# mdv_commutator.net
KiCad netlist of a schematic drawn in Altium Designer
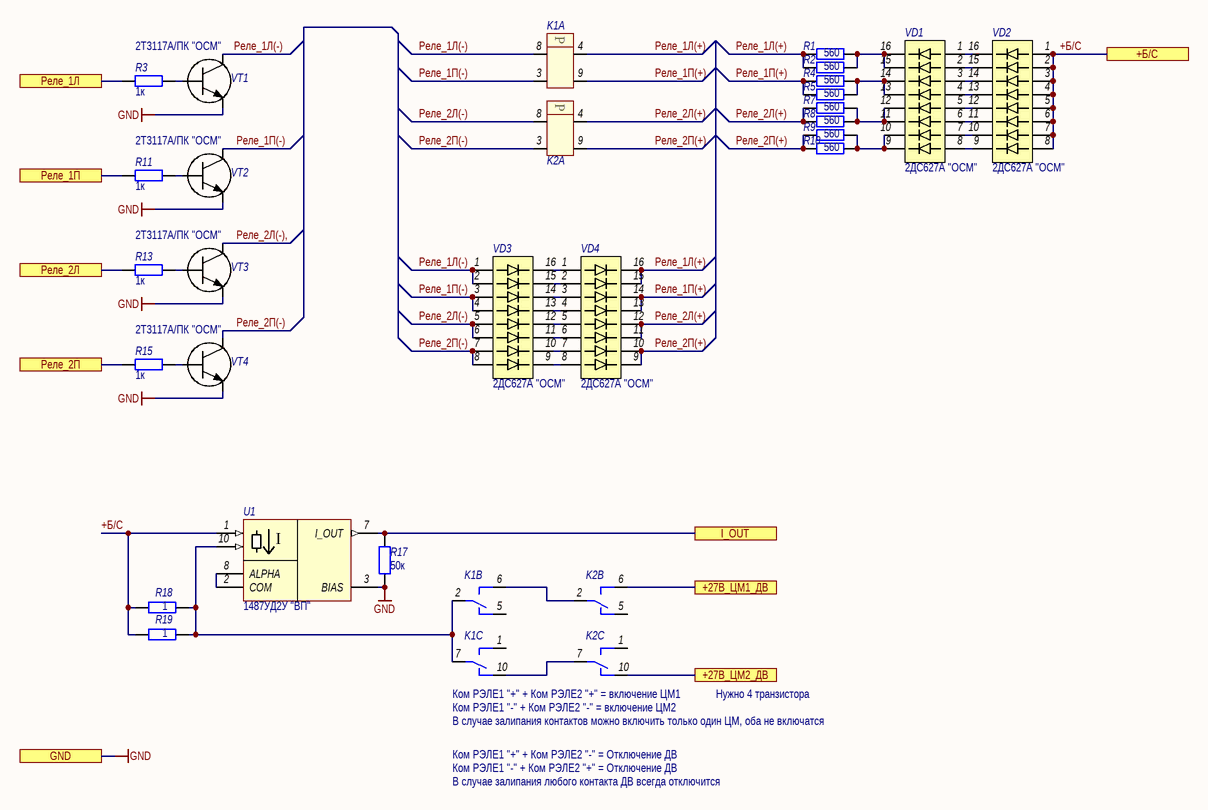
[diagram p0: mdv_commutator.SchDoc]

(export (version "E")
  (design (tool "Eeschema 10.0.6"))
  (components
    (comp (ref "K1")
      (value "RPS45-1-T-OS")
      (footprint "RPS-45-1")
      (description "Реле поляризованное")
      (libsource (lib "") (part "RPS45_1"))
    )
    (comp (ref "K2")
      (value "RPS45-1-T-OS")
      (footprint "RPS-45-1")
      (description "Реле поляризованное")
      (libsource (lib "Commutator") (part "RPS45"))
    )
    (comp (ref "R1")
      (value "560")
      (footprint "SMD_0805")
      (description "Resistor")
      (libsource (lib "Passive") (part "Resistor"))
    )
    (comp (ref "R2")
      (value "560")
      (footprint "SMD_0805")
      (description "Resistor")
      (libsource (lib "Passive") (part "Resistor"))
    )
    (comp (ref "R3")
      (value "1к")
      (footprint "SMD_0805")
      (description "Resistor")
      (libsource (lib "Passive") (part "Resistor"))
    )
    (comp (ref "R4")
      (value "560")
      (footprint "SMD_0805")
      (description "Resistor")
      (libsource (lib "Passive") (part "Resistor"))
    )
    (comp (ref "R5")
      (value "560")
      (footprint "SMD_0805")
      (description "Resistor")
      (libsource (lib "Passive") (part "Resistor"))
    )
    (comp (ref "R7")
      (value "560")
      (footprint "SMD_0805")
      (description "Resistor")
      (libsource (lib "Passive") (part "Resistor"))
    )
    (comp (ref "R8")
      (value "560")
      (footprint "SMD_0805")
      (description "Resistor")
      (libsource (lib "Passive") (part "Resistor"))
    )
    (comp (ref "R9")
      (value "560")
      (footprint "SMD_0805")
      (description "Resistor")
      (libsource (lib "Passive") (part "Resistor"))
    )
    (comp (ref "R10")
      (value "560")
      (footprint "SMD_0805")
      (description "Resistor")
      (libsource (lib "Passive") (part "Resistor"))
    )
    (comp (ref "R11")
      (value "1к")
      (footprint "SMD_0805")
      (description "Resistor")
      (libsource (lib "Passive") (part "Resistor"))
    )
    (comp (ref "R13")
      (value "1к")
      (footprint "SMD_0805")
      (description "Resistor")
      (libsource (lib "Passive") (part "Resistor"))
    )
    (comp (ref "R15")
      (value "1к")
      (footprint "SMD_0805")
      (description "Resistor")
      (libsource (lib "Passive") (part "Resistor"))
    )
    (comp (ref "R17")
      (value "50к")
      (footprint "SMD_0805")
      (description "Resistor")
      (libsource (lib "") (part "Resistor_2"))
    )
    (comp (ref "R18")
      (value "1")
      (footprint "SMD_0805")
      (description "Resistor")
      (libsource (lib "") (part "Resistor_1"))
    )
    (comp (ref "R19")
      (value "1")
      (footprint "SMD_0805")
      (description "Resistor")
      (libsource (lib "") (part "Resistor_1"))
    )
    (comp (ref "U1")
      (value "1487УД2У \"ВП\"")
      (footprint "FlatPack-10_MSOP-8")
      (libsource (lib "Power_Monitor") (part "AD8212S"))
    )
    (comp (ref "VD1")
      (value "2DS627A OSM")
      (footprint "401.16-3")
      (description "Диодная матрица")
      (fields (field (name "НАИМЕНОВАНИЕ") "2ДС627А \"ОСМ\""))
      (libsource (lib "Diod") (part "2DS627A"))
    )
    (comp (ref "VD2")
      (value "2DS627A OSM")
      (footprint "401.16-3")
      (description "Диодная матрица")
      (fields (field (name "НАИМЕНОВАНИЕ") "2ДС627А \"ОСМ\""))
      (libsource (lib "Diod") (part "2DS627A"))
    )
    (comp (ref "VD3")
      (value "2DS627A OSM")
      (footprint "401.16-3")
      (description "Диодная матрица")
      (fields (field (name "НАИМЕНОВАНИЕ") "2ДС627А \"ОСМ\""))
      (libsource (lib "Diod") (part "2DS627A"))
    )
    (comp (ref "VD4")
      (value "2DS627A OSM")
      (footprint "401.16-3")
      (description "Диодная матрица")
      (fields (field (name "НАИМЕНОВАНИЕ") "2ДС627А \"ОСМ\""))
      (libsource (lib "Diod") (part "2DS627A"))
    )
    (comp (ref "VT1")
      (value "2T3117A")
      (footprint "TO-18")
      (description "Кремниевый биполярный\r\nэпитаксиально-планарный\r\nn-p-n транзистор")
      (fields (field (name "НАИМЕНОВАНИЕ") "2Т3117А/ПК \"ОСМ\""))
      (libsource (lib "Transistor") (part "2T3117A"))
    )
    (comp (ref "VT2")
      (value "2T3117A")
      (footprint "TO-18")
      (description "Кремниевый биполярный\r\nэпитаксиально-планарный\r\nn-p-n транзистор")
      (fields (field (name "НАИМЕНОВАНИЕ") "2Т3117А/ПК \"ОСМ\""))
      (libsource (lib "Transistor") (part "2T3117A"))
    )
    (comp (ref "VT3")
      (value "2T3117A")
      (footprint "TO-18")
      (description "Кремниевый биполярный\r\nэпитаксиально-планарный\r\nn-p-n транзистор")
      (fields (field (name "НАИМЕНОВАНИЕ") "2Т3117А/ПК \"ОСМ\""))
      (libsource (lib "Transistor") (part "2T3117A"))
    )
    (comp (ref "VT4")
      (value "2T3117A")
      (footprint "TO-18")
      (description "Кремниевый биполярный\r\nэпитаксиально-планарный\r\nn-p-n транзистор")
      (fields (field (name "НАИМЕНОВАНИЕ") "2Т3117А/ПК \"ОСМ\""))
      (libsource (lib "Transistor") (part "2T3117A"))
    )
  )
  (nets
    (net (code "1") (name "/+27В_ЦМ1_ДВ") (class "Default")
      (node (ref "K2") (pin "6") (pinfunction "6_6") (pintype "passive"))
    )
    (net (code "2") (name "/+27В_ЦМ2_ДВ") (class "Default")
      (node (ref "K2") (pin "10") (pinfunction "10_10") (pintype "passive"))
    )
    (net (code "3") (name "/+Б{slash}С") (class "Default")
      (node (ref "R18") (pin "2") (pinfunction "2_2") (pintype "passive"))
      (node (ref "R19") (pin "2") (pinfunction "2_2") (pintype "passive"))
      (node (ref "U1") (pin "1") (pinfunction "V+_1") (pintype "input"))
      (node (ref "VD2") (pin "1") (pinfunction "1A_1") (pintype "passive"))
      (node (ref "VD2") (pin "2") (pinfunction "1B_2") (pintype "passive"))
      (node (ref "VD2") (pin "3") (pinfunction "1C_3") (pintype "passive"))
      (node (ref "VD2") (pin "4") (pinfunction "1D_4") (pintype "passive"))
      (node (ref "VD2") (pin "5") (pinfunction "1E_5") (pintype "passive"))
      (node (ref "VD2") (pin "6") (pinfunction "1F_6") (pintype "passive"))
      (node (ref "VD2") (pin "7") (pinfunction "1G_7") (pintype "passive"))
      (node (ref "VD2") (pin "8") (pinfunction "1H_8") (pintype "passive"))
    )
    (net (code "4") (name "/I_OUT") (class "Default")
      (node (ref "R17") (pin "2") (pinfunction "2_2") (pintype "passive"))
      (node (ref "U1") (pin "7") (pinfunction "I_OUT_7") (pintype "output"))
    )
    (net (code "5") (name "/Реле_1Л") (class "Default")
      (node (ref "R3") (pin "1") (pinfunction "1_1") (pintype "passive"))
    )
    (net (code "6") (name "/Реле_1Л(+)") (class "Default")
      (node (ref "K1") (pin "4") (pinfunction "4_4") (pintype "passive"))
      (node (ref "R1") (pin "1") (pinfunction "1_1") (pintype "passive"))
      (node (ref "R2") (pin "1") (pinfunction "1_1") (pintype "passive"))
      (node (ref "VD4") (pin "15") (pinfunction "2B_15") (pintype "passive"))
      (node (ref "VD4") (pin "16") (pinfunction "2A_16") (pintype "passive"))
    )
    (net (code "7") (name "/Реле_1Л(-)") (class "Default")
      (node (ref "K1") (pin "8") (pinfunction "8_8") (pintype "passive"))
      (node (ref "VD3") (pin "1") (pinfunction "1A_1") (pintype "passive"))
      (node (ref "VD3") (pin "2") (pinfunction "1B_2") (pintype "passive"))
      (node (ref "VT1") (pin "3") (pinfunction "COLLECTOR_3") (pintype "passive"))
    )
    (net (code "8") (name "/Реле_1П") (class "Default")
      (node (ref "R11") (pin "1") (pinfunction "1_1") (pintype "passive"))
    )
    (net (code "9") (name "/Реле_1П(+)") (class "Default")
      (node (ref "K1") (pin "9") (pinfunction "9_9") (pintype "passive"))
      (node (ref "R4") (pin "1") (pinfunction "1_1") (pintype "passive"))
      (node (ref "R5") (pin "1") (pinfunction "1_1") (pintype "passive"))
      (node (ref "VD4") (pin "13") (pinfunction "2D_13") (pintype "passive"))
      (node (ref "VD4") (pin "14") (pinfunction "2C_14") (pintype "passive"))
    )
    (net (code "10") (name "/Реле_1П(-)") (class "Default")
      (node (ref "K1") (pin "3") (pinfunction "3_3") (pintype "passive"))
      (node (ref "VD3") (pin "3") (pinfunction "1C_3") (pintype "passive"))
      (node (ref "VD3") (pin "4") (pinfunction "1D_4") (pintype "passive"))
      (node (ref "VT2") (pin "3") (pinfunction "COLLECTOR_3") (pintype "passive"))
    )
    (net (code "11") (name "/Реле_2Л") (class "Default")
      (node (ref "R13") (pin "1") (pinfunction "1_1") (pintype "passive"))
    )
    (net (code "12") (name "/Реле_2Л(+)") (class "Default")
      (node (ref "K2") (pin "4") (pinfunction "4_4") (pintype "passive"))
      (node (ref "R7") (pin "1") (pinfunction "1_1") (pintype "passive"))
      (node (ref "R8") (pin "1") (pinfunction "1_1") (pintype "passive"))
      (node (ref "VD4") (pin "11") (pinfunction "2F_11") (pintype "passive"))
      (node (ref "VD4") (pin "12") (pinfunction "2E_12") (pintype "passive"))
    )
    (net (code "13") (name "/Реле_2Л(-)") (class "Default")
      (node (ref "K2") (pin "8") (pinfunction "8_8") (pintype "passive"))
      (node (ref "VD3") (pin "5") (pinfunction "1E_5") (pintype "passive"))
      (node (ref "VD3") (pin "6") (pinfunction "1F_6") (pintype "passive"))
    )
    (net (code "14") (name "/Реле_2Л(-),") (class "Default")
      (node (ref "VT3") (pin "3") (pinfunction "COLLECTOR_3") (pintype "passive"))
    )
    (net (code "15") (name "/Реле_2П") (class "Default")
      (node (ref "R15") (pin "1") (pinfunction "1_1") (pintype "passive"))
    )
    (net (code "16") (name "/Реле_2П(+)") (class "Default")
      (node (ref "K2") (pin "9") (pinfunction "9_9") (pintype "passive"))
      (node (ref "R10") (pin "1") (pinfunction "1_1") (pintype "passive"))
      (node (ref "R9") (pin "1") (pinfunction "1_1") (pintype "passive"))
      (node (ref "VD4") (pin "10") (pinfunction "2G_10") (pintype "passive"))
      (node (ref "VD4") (pin "9") (pinfunction "2G_9") (pintype "passive"))
    )
    (net (code "17") (name "/Реле_2П(-)") (class "Default")
      (node (ref "K2") (pin "3") (pinfunction "3_3") (pintype "passive"))
      (node (ref "VD3") (pin "7") (pinfunction "1G_7") (pintype "passive"))
      (node (ref "VD3") (pin "8") (pinfunction "1H_8") (pintype "passive"))
      (node (ref "VT4") (pin "3") (pinfunction "COLLECTOR_3") (pintype "passive"))
    )
    (net (code "18") (name "GND") (class "Default")
      (node (ref "R17") (pin "1") (pinfunction "1_1") (pintype "passive"))
      (node (ref "U1") (pin "3") (pinfunction "BIAS_3") (pintype "open_collector"))
      (node (ref "VT1") (pin "1") (pinfunction "EMITTER_1") (pintype "passive"))
      (node (ref "VT2") (pin "1") (pinfunction "EMITTER_1") (pintype "passive"))
      (node (ref "VT3") (pin "1") (pinfunction "EMITTER_1") (pintype "passive"))
      (node (ref "VT4") (pin "1") (pinfunction "EMITTER_1") (pintype "passive"))
    )
    (net (code "19") (name "Net-(K1-Pad6)") (class "Default")
      (node (ref "K1") (pin "6") (pinfunction "6_6") (pintype "passive"))
      (node (ref "K2") (pin "2") (pinfunction "2_2") (pintype "passive"))
    )
    (net (code "20") (name "Net-(K1-Pad10)") (class "Default")
      (node (ref "K1") (pin "10") (pinfunction "10_10") (pintype "passive"))
      (node (ref "K2") (pin "7") (pinfunction "7_7") (pintype "passive"))
    )
    (net (code "21") (name "Net-(R10-Pad2)") (class "Default")
      (node (ref "R10") (pin "2") (pinfunction "2_2") (pintype "passive"))
      (node (ref "R9") (pin "2") (pinfunction "2_2") (pintype "passive"))
      (node (ref "VD1") (pin "10") (pinfunction "2G_10") (pintype "passive"))
      (node (ref "VD1") (pin "9") (pinfunction "2G_9") (pintype "passive"))
    )
    (net (code "22") (name "Net-(U1-ALPHA)") (class "Default")
      (node (ref "U1") (pin "2") (pinfunction "COM_2") (pintype "open_collector"))
      (node (ref "U1") (pin "8") (pinfunction "ALPHA_8") (pintype "open_collector"))
    )
    (net (code "23") (name "Net-(U1-V_SENSE)") (class "Default")
      (node (ref "K1") (pin "2") (pinfunction "2_2") (pintype "passive"))
      (node (ref "K1") (pin "7") (pinfunction "7_7") (pintype "passive"))
      (node (ref "R18") (pin "1") (pinfunction "1_1") (pintype "passive"))
      (node (ref "R19") (pin "1") (pinfunction "1_1") (pintype "passive"))
      (node (ref "U1") (pin "10") (pinfunction "V_SENSE_10") (pintype "input"))
    )
    (net (code "24") (name "Net-(VD1-1A)") (class "Default")
      (node (ref "VD1") (pin "1") (pinfunction "1A_1") (pintype "passive"))
      (node (ref "VD2") (pin "16") (pinfunction "2A_16") (pintype "passive"))
    )
    (net (code "25") (name "Net-(VD1-1B)") (class "Default")
      (node (ref "VD1") (pin "2") (pinfunction "1B_2") (pintype "passive"))
      (node (ref "VD2") (pin "15") (pinfunction "2B_15") (pintype "passive"))
    )
    (net (code "26") (name "Net-(VD1-1C)") (class "Default")
      (node (ref "VD1") (pin "3") (pinfunction "1C_3") (pintype "passive"))
      (node (ref "VD2") (pin "14") (pinfunction "2C_14") (pintype "passive"))
    )
    (net (code "27") (name "Net-(VD1-1D)") (class "Default")
      (node (ref "VD1") (pin "4") (pinfunction "1D_4") (pintype "passive"))
      (node (ref "VD2") (pin "13") (pinfunction "2D_13") (pintype "passive"))
    )
    (net (code "28") (name "Net-(VD1-1E)") (class "Default")
      (node (ref "VD1") (pin "5") (pinfunction "1E_5") (pintype "passive"))
      (node (ref "VD2") (pin "12") (pinfunction "2E_12") (pintype "passive"))
    )
    (net (code "29") (name "Net-(VD1-1F)") (class "Default")
      (node (ref "VD1") (pin "6") (pinfunction "1F_6") (pintype "passive"))
      (node (ref "VD2") (pin "11") (pinfunction "2F_11") (pintype "passive"))
    )
    (net (code "30") (name "Net-(VD1-1G)") (class "Default")
      (node (ref "VD1") (pin "7") (pinfunction "1G_7") (pintype "passive"))
      (node (ref "VD2") (pin "10") (pinfunction "2G_10") (pintype "passive"))
    )
    (net (code "31") (name "Net-(VD1-1H)") (class "Default")
      (node (ref "VD1") (pin "8") (pinfunction "1H_8") (pintype "passive"))
      (node (ref "VD2") (pin "9") (pinfunction "2G_9") (pintype "passive"))
    )
    (net (code "32") (name "Net-(VD1-2A)") (class "Default")
      (node (ref "R1") (pin "2") (pinfunction "2_2") (pintype "passive"))
      (node (ref "R2") (pin "2") (pinfunction "2_2") (pintype "passive"))
      (node (ref "VD1") (pin "15") (pinfunction "2B_15") (pintype "passive"))
      (node (ref "VD1") (pin "16") (pinfunction "2A_16") (pintype "passive"))
    )
    (net (code "33") (name "Net-(VD1-2C)") (class "Default")
      (node (ref "R4") (pin "2") (pinfunction "2_2") (pintype "passive"))
      (node (ref "R5") (pin "2") (pinfunction "2_2") (pintype "passive"))
      (node (ref "VD1") (pin "13") (pinfunction "2D_13") (pintype "passive"))
      (node (ref "VD1") (pin "14") (pinfunction "2C_14") (pintype "passive"))
    )
    (net (code "34") (name "Net-(VD1-2E)") (class "Default")
      (node (ref "R7") (pin "2") (pinfunction "2_2") (pintype "passive"))
      (node (ref "R8") (pin "2") (pinfunction "2_2") (pintype "passive"))
      (node (ref "VD1") (pin "11") (pinfunction "2F_11") (pintype "passive"))
      (node (ref "VD1") (pin "12") (pinfunction "2E_12") (pintype "passive"))
    )
    (net (code "35") (name "Net-(VD3-2A)") (class "Default")
      (node (ref "VD3") (pin "16") (pinfunction "2A_16") (pintype "passive"))
      (node (ref "VD4") (pin "1") (pinfunction "1A_1") (pintype "passive"))
    )
    (net (code "36") (name "Net-(VD3-2B)") (class "Default")
      (node (ref "VD3") (pin "15") (pinfunction "2B_15") (pintype "passive"))
      (node (ref "VD4") (pin "2") (pinfunction "1B_2") (pintype "passive"))
    )
    (net (code "37") (name "Net-(VD3-2C)") (class "Default")
      (node (ref "VD3") (pin "14") (pinfunction "2C_14") (pintype "passive"))
      (node (ref "VD4") (pin "3") (pinfunction "1C_3") (pintype "passive"))
    )
    (net (code "38") (name "Net-(VD3-2D)") (class "Default")
      (node (ref "VD3") (pin "13") (pinfunction "2D_13") (pintype "passive"))
      (node (ref "VD4") (pin "4") (pinfunction "1D_4") (pintype "passive"))
    )
    (net (code "39") (name "Net-(VD3-2E)") (class "Default")
      (node (ref "VD3") (pin "12") (pinfunction "2E_12") (pintype "passive"))
      (node (ref "VD4") (pin "5") (pinfunction "1E_5") (pintype "passive"))
    )
    (net (code "40") (name "Net-(VD3-2F)") (class "Default")
      (node (ref "VD3") (pin "11") (pinfunction "2F_11") (pintype "passive"))
      (node (ref "VD4") (pin "6") (pinfunction "1F_6") (pintype "passive"))
    )
    (net (code "41") (name "Net-(VD4-1G)") (class "Default")
      (node (ref "VD3") (pin "10") (pinfunction "2G_10") (pintype "passive"))
      (node (ref "VD4") (pin "7") (pinfunction "1G_7") (pintype "passive"))
    )
    (net (code "42") (name "Net-(VD4-1H)") (class "Default")
      (node (ref "VD3") (pin "9") (pinfunction "2G_9") (pintype "passive"))
      (node (ref "VD4") (pin "8") (pinfunction "1H_8") (pintype "passive"))
    )
    (net (code "43") (name "Net-(VT1-BASE)") (class "Default")
      (node (ref "R3") (pin "2") (pinfunction "2_2") (pintype "passive"))
      (node (ref "VT1") (pin "2") (pinfunction "BASE_2") (pintype "passive"))
    )
    (net (code "44") (name "Net-(VT2-BASE)") (class "Default")
      (node (ref "R11") (pin "2") (pinfunction "2_2") (pintype "passive"))
      (node (ref "VT2") (pin "2") (pinfunction "BASE_2") (pintype "passive"))
    )
    (net (code "45") (name "Net-(VT3-BASE)") (class "Default")
      (node (ref "R13") (pin "2") (pinfunction "2_2") (pintype "passive"))
      (node (ref "VT3") (pin "2") (pinfunction "BASE_2") (pintype "passive"))
    )
    (net (code "46") (name "Net-(VT4-BASE)") (class "Default")
      (node (ref "R15") (pin "2") (pinfunction "2_2") (pintype "passive"))
      (node (ref "VT4") (pin "2") (pinfunction "BASE_2") (pintype "passive"))
    )
    (net (code "47") (name "unconnected-(K1-Pad1)") (class "Default")
      (node (ref "K1") (pin "1") (pinfunction "1_1") (pintype "passive"))
    )
    (net (code "48") (name "unconnected-(K1-Pad5)") (class "Default")
      (node (ref "K1") (pin "5") (pinfunction "5_5") (pintype "passive"))
    )
    (net (code "49") (name "unconnected-(K2-Pad1)") (class "Default")
      (node (ref "K2") (pin "1") (pinfunction "1_1") (pintype "passive"))
    )
    (net (code "50") (name "unconnected-(K2-Pad5)") (class "Default")
      (node (ref "K2") (pin "5") (pinfunction "5_5") (pintype "passive"))
    )
  )
)
